# Cable.net
KiCad netlist of a schematic drawn in Altium Designer
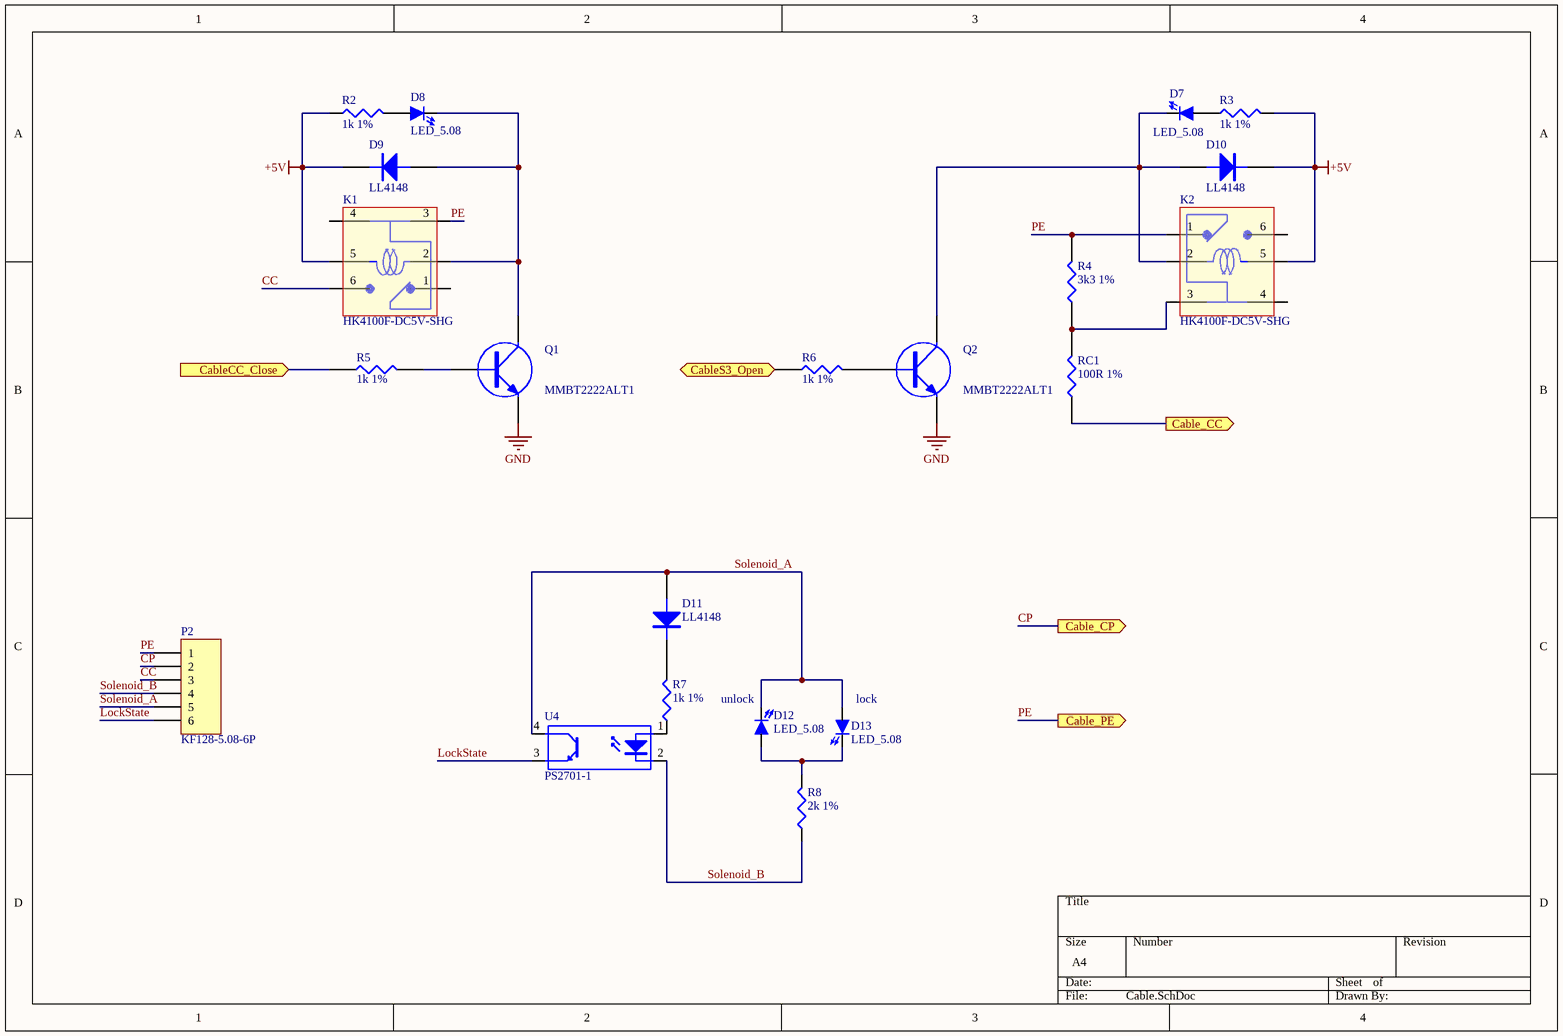
[diagram p0: Cable.SchDoc]

(export (version "E")
  (design (tool "Eeschema 10.0.6"))
  (components
    (comp (ref "D7")
      (value "LED_5.08")
      (footprint "UserPcbLib:LED5.08/2.54-2")
      (description "Through hole LED dia.5.08")
      (libsource (lib "UserSchlib") (part "LED_5.08"))
    )
    (comp (ref "D8")
      (value "LED_5.08")
      (footprint "UserPcbLib:LED5.08/2.54-2")
      (description "Through hole LED dia.5.08")
      (libsource (lib "UserSchlib") (part "LED_5.08"))
    )
    (comp (ref "D9")
      (value "LL4148")
      (footprint "MELF - Diode:MELF-D3513-1405")
      (description "Diode")
      (libsource (lib "*") (part "DIODE"))
    )
    (comp (ref "D10")
      (value "LL4148")
      (footprint "MELF - Diode:MELF-D3513-1405")
      (description "Diode")
      (libsource (lib "*") (part "DIODE"))
    )
    (comp (ref "D11")
      (value "LL4148")
      (footprint "MELF - Diode:MELF-D3513-1405")
      (description "Diode")
      (libsource (lib "*") (part "DIODE"))
    )
    (comp (ref "D12")
      (value "LED_5.08")
      (footprint "UserPcbLib:LED5.08/2.54-2")
      (description "Through hole LED dia.5.08")
      (libsource (lib "UserSchlib") (part "LED_5.08"))
    )
    (comp (ref "D13")
      (value "LED_5.08")
      (footprint "UserPcbLib:LED5.08/2.54-2")
      (description "Through hole LED dia.5.08")
      (libsource (lib "UserSchlib") (part "LED_5.08"))
    )
    (comp (ref "K1")
      (value "HK4100F-DC5V-SHG")
      (footprint "UserPcbLib:HK4100F-DC5V-SHG")
      (description "HUI KE DC5V relay")
      (libsource (lib "") (part "HK4100F-DC5V-SHG_1"))
    )
    (comp (ref "K2")
      (value "HK4100F-DC5V-SHG")
      (footprint "UserPcbLib:HK4100F-DC5V-SHG")
      (description "HUI KE DC5V relay")
      (libsource (lib "UserSchlib") (part "HK4100F-DC5V-SHG"))
    )
    (comp (ref "P2")
      (value "KF128-5.08-6P")
      (footprint "UserPcbLib:KF128-5.08-6P")
      (description "Pilot connectors")
      (fields (field (name "PUBLISHER") "Altium Limited"))
      (libsource (lib "Miscellaneous Connectors") (part "Header 6"))
    )
    (comp (ref "Q1") (value "MMBT2222ALT1") (footprint "SOT23_M:SOT23-3M") (libsource (lib "*") (part "NPN")))
    (comp (ref "Q2") (value "MMBT2222ALT1") (footprint "SOT23_M:SOT23-3M") (libsource (lib "*") (part "NPN")))
    (comp (ref "R2")
      (value "1k 1%")
      (footprint "Chip_Resistor_N:RESC2012N")
      (description "Resistor")
      (libsource (lib "Miscellaneous Devices") (part "Res3"))
    )
    (comp (ref "R3")
      (value "1k 1%")
      (footprint "Chip_Resistor_N:RESC2012N")
      (description "Resistor")
      (libsource (lib "Miscellaneous Devices") (part "Res3"))
    )
    (comp (ref "R4")
      (value "3k3 1%")
      (footprint "Chip_Resistor_N:RESC2012N")
      (libsource (lib "*") (part "RES1"))
    )
    (comp (ref "R5")
      (value "1k 1%")
      (footprint "Chip_Resistor_N:RESC2012N")
      (libsource (lib "*") (part "RES1"))
    )
    (comp (ref "R6")
      (value "1k 1%")
      (footprint "Chip_Resistor_N:RESC2012N")
      (libsource (lib "*") (part "RES1"))
    )
    (comp (ref "R7")
      (value "1k 1%")
      (footprint "Chip_Resistor_N:RESC2012N")
      (description "Resistor")
      (libsource (lib "Miscellaneous Devices") (part "Res3"))
    )
    (comp (ref "R8")
      (value "2k 1%")
      (footprint "Chip_Resistor_N:RESC2012N")
      (description "Resistor")
      (libsource (lib "Miscellaneous Devices") (part "Res3"))
    )
    (comp (ref "RC1")
      (value "100R 1%")
      (footprint "Chip_Resistor_N:RESC2012N")
      (libsource (lib "*") (part "RES1"))
    )
    (comp (ref "U4")
      (value "PS2701-1")
      (footprint "UserPcbLib:SOP4 for PS2701-1")
      (description "Photocoupler")
      (libsource (lib "UserSchlib") (part "PS2701-1"))
    )
  )
  (nets
    (net (code "1") (name "+5V") (class "Default")
      (node (ref "D10") (pin "2") (pinfunction "K_2") (pintype "passive"))
      (node (ref "D9") (pin "2") (pinfunction "K_2") (pintype "passive"))
      (node (ref "K1") (pin "5") (pinfunction "5_5") (pintype "passive"))
      (node (ref "K2") (pin "5") (pinfunction "5_5") (pintype "passive"))
      (node (ref "R2") (pin "1") (pinfunction "1_1") (pintype "passive"))
      (node (ref "R3") (pin "2") (pinfunction "2_2") (pintype "passive"))
    )
    (net (code "2") (name "/CC") (class "Default")
      (node (ref "K1") (pin "6") (pinfunction "6_6") (pintype "passive"))
      (node (ref "P2") (pin "3") (pinfunction "3_3") (pintype "passive"))
    )
    (net (code "3") (name "/CP") (class "Default")
      (node (ref "P2") (pin "2") (pinfunction "2_2") (pintype "passive"))
    )
    (net (code "4") (name "/CableCC_Close") (class "Default")
      (node (ref "R5") (pin "1") (pinfunction "1_1") (pintype "passive"))
    )
    (net (code "5") (name "/CableS3_Open") (class "Default")
      (node (ref "R6") (pin "1") (pinfunction "1_1") (pintype "passive"))
    )
    (net (code "6") (name "/Cable_CC") (class "Default")
      (node (ref "RC1") (pin "1") (pinfunction "1_1") (pintype "passive"))
    )
    (net (code "7") (name "/LockState") (class "Default")
      (node (ref "P2") (pin "6") (pinfunction "6_6") (pintype "passive"))
      (node (ref "U4") (pin "3") (pinfunction "E_3") (pintype "passive"))
    )
    (net (code "8") (name "/PE") (class "Default")
      (node (ref "K1") (pin "3") (pinfunction "3_3") (pintype "passive"))
      (node (ref "K2") (pin "1") (pinfunction "1_1") (pintype "passive"))
      (node (ref "P2") (pin "1") (pinfunction "1_1") (pintype "passive"))
      (node (ref "R4") (pin "2") (pinfunction "2_2") (pintype "passive"))
    )
    (net (code "9") (name "/Solenoid_A") (class "Default")
      (node (ref "D11") (pin "1") (pinfunction "A_1") (pintype "passive"))
      (node (ref "D12") (pin "2") (pinfunction "K_2") (pintype "passive"))
      (node (ref "D13") (pin "1") (pinfunction "A_1") (pintype "passive"))
      (node (ref "P2") (pin "5") (pinfunction "5_5") (pintype "passive"))
      (node (ref "U4") (pin "4") (pinfunction "C_4") (pintype "passive"))
    )
    (net (code "10") (name "/Solenoid_B") (class "Default")
      (node (ref "P2") (pin "4") (pinfunction "4_4") (pintype "passive"))
      (node (ref "R8") (pin "1") (pinfunction "1_1") (pintype "passive"))
      (node (ref "U4") (pin "2") (pinfunction "K_2") (pintype "passive"))
    )
    (net (code "11") (name "GND") (class "Default")
      (node (ref "Q1") (pin "2") (pinfunction "E_2") (pintype "passive"))
      (node (ref "Q2") (pin "2") (pinfunction "E_2") (pintype "passive"))
    )
    (net (code "12") (name "Net-(D7-A)") (class "Default")
      (node (ref "D7") (pin "1") (pinfunction "A_1") (pintype "passive"))
      (node (ref "R3") (pin "1") (pinfunction "1_1") (pintype "passive"))
    )
    (net (code "13") (name "Net-(D8-A)") (class "Default")
      (node (ref "D8") (pin "1") (pinfunction "A_1") (pintype "passive"))
      (node (ref "R2") (pin "2") (pinfunction "2_2") (pintype "passive"))
    )
    (net (code "14") (name "Net-(D8-K)") (class "Default")
      (node (ref "D8") (pin "2") (pinfunction "K_2") (pintype "passive"))
      (node (ref "D9") (pin "1") (pinfunction "A_1") (pintype "passive"))
      (node (ref "K1") (pin "2") (pinfunction "2_2") (pintype "passive"))
      (node (ref "Q1") (pin "3") (pinfunction "C_3") (pintype "passive"))
    )
    (net (code "15") (name "Net-(D10-A)") (class "Default")
      (node (ref "D10") (pin "1") (pinfunction "A_1") (pintype "passive"))
      (node (ref "D7") (pin "2") (pinfunction "K_2") (pintype "passive"))
      (node (ref "K2") (pin "2") (pinfunction "2_2") (pintype "passive"))
      (node (ref "Q2") (pin "3") (pinfunction "C_3") (pintype "passive"))
    )
    (net (code "16") (name "Net-(D11-K)") (class "Default")
      (node (ref "D11") (pin "2") (pinfunction "K_2") (pintype "passive"))
      (node (ref "R7") (pin "2") (pinfunction "2_2") (pintype "passive"))
    )
    (net (code "17") (name "Net-(D12-A)") (class "Default")
      (node (ref "D12") (pin "1") (pinfunction "A_1") (pintype "passive"))
      (node (ref "D13") (pin "2") (pinfunction "K_2") (pintype "passive"))
      (node (ref "R8") (pin "2") (pinfunction "2_2") (pintype "passive"))
    )
    (net (code "18") (name "Net-(K2-Pad3)") (class "Default")
      (node (ref "K2") (pin "3") (pinfunction "3_3") (pintype "passive"))
      (node (ref "R4") (pin "1") (pinfunction "1_1") (pintype "passive"))
      (node (ref "RC1") (pin "2") (pinfunction "2_2") (pintype "passive"))
    )
    (net (code "19") (name "Net-(Q1-B)") (class "Default")
      (node (ref "Q1") (pin "1") (pinfunction "B_1") (pintype "passive"))
      (node (ref "R5") (pin "2") (pinfunction "2_2") (pintype "passive"))
    )
    (net (code "20") (name "Net-(Q2-B)") (class "Default")
      (node (ref "Q2") (pin "1") (pinfunction "B_1") (pintype "passive"))
      (node (ref "R6") (pin "2") (pinfunction "2_2") (pintype "passive"))
    )
    (net (code "21") (name "Net-(U4-A)") (class "Default")
      (node (ref "R7") (pin "1") (pinfunction "1_1") (pintype "passive"))
      (node (ref "U4") (pin "1") (pinfunction "A_1") (pintype "passive"))
    )
    (net (code "22") (name "unconnected-(K1-Pad1)") (class "Default")
      (node (ref "K1") (pin "1") (pinfunction "1_1") (pintype "passive"))
    )
    (net (code "23") (name "unconnected-(K1-Pad4)") (class "Default")
      (node (ref "K1") (pin "4") (pinfunction "4_4") (pintype "passive"))
    )
    (net (code "24") (name "unconnected-(K2-Pad4)") (class "Default")
      (node (ref "K2") (pin "4") (pinfunction "4_4") (pintype "passive"))
    )
    (net (code "25") (name "unconnected-(K2-Pad6)") (class "Default")
      (node (ref "K2") (pin "6") (pinfunction "6_6") (pintype "passive"))
    )
  )
)
